# 3V3_VoltageReg.net
KiCad netlist of a schematic drawn in Altium Designer
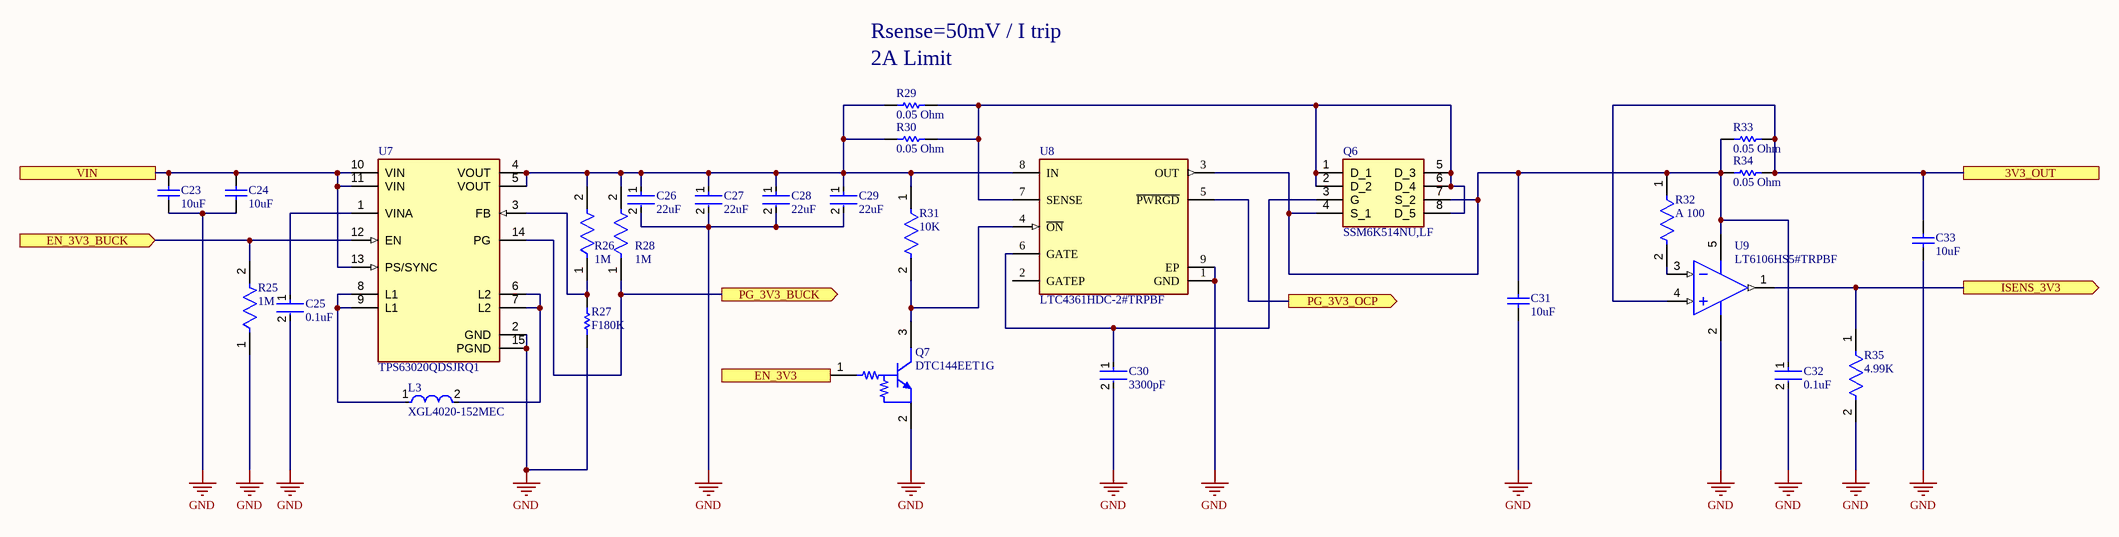
[diagram p0: 3V3_VoltageReg.SchDoc]

(export (version "E")
  (design (tool "Eeschema 10.0.6"))
  (components
    (comp (ref "C23")
      (value "10uF")
      (footprint "CAPC2013X140X45NL15T25")
      (fields (field (name "PART NUMBER") "GRM21BR71A106KE51L") (field (name "MANUFACTURER") "Murata"))
      (libsource (lib "Altium Content Vault") (part "CAP"))
    )
    (comp (ref "C24")
      (value "10uF")
      (footprint "CAPC2013X140X45NL15T25")
      (fields (field (name "PART NUMBER") "GRM21BR71A106KE51L") (field (name "MANUFACTURER") "Murata"))
      (libsource (lib "Altium Content Vault") (part "CAP"))
    )
    (comp (ref "C25")
      (value "0.1uF")
      (footprint "FP-C0603C-CF-MFG")
      (description "CAP CER 0.1UF 50V X7R 0603")
      (fields (field (name "TOLERANCE") "0.1") (field (name "MANUFACTURER") "KEMET"))
      (libsource (lib "Altium Content Vault") (part "b4654b650e69147ec39a6b967a45e02"))
    )
    (comp (ref "C26")
      (value "22uF")
      (footprint "FP-GRM21B-0_2-e0_2_0_7-IPC_C")
      (description "Chip Multilayer Ceramic Capacitors for General Purpose, 0805, 22uF, X7T, +22%/-33%, 20%, 10V")
      (fields (field (name "VOLTAGE") "10V") (field (name "TOLERANCE") "20%"))
      (libsource (lib "Altium Content Vault") (part "b4654b650e69147ec39a6b967a45e02"))
    )
    (comp (ref "C27")
      (value "22uF")
      (footprint "FP-GRM21B-0_2-e0_2_0_7-IPC_C")
      (description "Chip Multilayer Ceramic Capacitors for General Purpose, 0805, 22uF, X7T, +22%/-33%, 20%, 10V")
      (fields (field (name "VOLTAGE") "10V") (field (name "TOLERANCE") "20%"))
      (libsource (lib "Altium Content Vault") (part "b4654b650e69147ec39a6b967a45e02"))
    )
    (comp (ref "C28")
      (value "22uF")
      (footprint "FP-GRM21B-0_2-e0_2_0_7-IPC_C")
      (description "Chip Multilayer Ceramic Capacitors for General Purpose, 0805, 22uF, X7T, +22%/-33%, 20%, 10V")
      (fields (field (name "VOLTAGE") "10V") (field (name "TOLERANCE") "20%"))
      (libsource (lib "Altium Content Vault") (part "b4654b650e69147ec39a6b967a45e02"))
    )
    (comp (ref "C29")
      (value "22uF")
      (footprint "FP-GRM21B-0_2-e0_2_0_7-IPC_C")
      (description "Chip Multilayer Ceramic Capacitors for General Purpose, 0805, 22uF, X7T, +22%/-33%, 20%, 10V")
      (fields (field (name "VOLTAGE") "10V") (field (name "TOLERANCE") "20%"))
      (libsource (lib "Altium Content Vault") (part "b4654b650e69147ec39a6b967a45e02"))
    )
    (comp (ref "C30")
      (value "3300pF")
      (footprint "FP-C0603C-CF-MFG")
      (description "CAP CER 3300PF 50V 5% X7R 0603")
      (fields
        (field (name "MANUFACTURER PART NUMBER") "C0603C332J5RACTU")
        (field (name "MANUFACTURER") "KEMET")
      )
      (libsource (lib "Altium Content Vault") (part "b4654b650e69147ec39a6b967a45e02"))
    )
    (comp (ref "C31")
      (value "10uF")
      (footprint "CAPC2013X140X45NL15T25")
      (fields (field (name "PART NUMBER") "GRM21BR71A106KE51L") (field (name "MANUFACTURER") "Murata"))
      (libsource (lib "Altium Content Vault") (part "CAP"))
    )
    (comp (ref "C32")
      (value "0.1uF")
      (footprint "FP-C0603C-CF-MFG")
      (description "CAP CER 0.1UF 50V X7R 0603")
      (fields (field (name "TOLERANCE") "0.1") (field (name "MANUFACTURER") "KEMET"))
      (libsource (lib "Altium Content Vault") (part "b4654b650e69147ec39a6b967a45e02"))
    )
    (comp (ref "C33")
      (value "10uF")
      (footprint "CAPC2013X140X45NL15T25")
      (fields (field (name "PART NUMBER") "GRM21BR71A106KE51L") (field (name "MANUFACTURER") "Murata"))
      (libsource (lib "Altium Content Vault") (part "CAP"))
    )
    (comp (ref "L3")
      (value "XGL4020-152MEC")
      (footprint "FP-XGL4020-MFG")
      (description "Shielded Power Inductors")
      (fields (field (name "MANUFACTURER") "Coilcraft") (field (name "TOLERANCE") "20%"))
      (libsource (lib "Altium Content Vault") (part "725321dda6339637d4d059423bc1c3c"))
    )
    (comp (ref "Q6")
      (value "SSM6K514NU,LF")
      (footprint "SamacSys:UDFN6B")
      (description "MOSFET (N-Channel)")
      (fields (field (name "MOUSER PART NUMBER") "757-SSM6K514NULF"))
      (libsource (lib "*") (part "SSM6K514NU,LF"))
    )
    (comp (ref "Q7")
      (value "DTC144EET1G")
      (footprint "ONSC-SC-75-3-463-01_V")
      (fields (field (name "MANUFACTURER") "On Semiconductor"))
      (libsource (lib "Altium Content Vault") (part "ONSC-BRT-NPN-B1E2C3-3"))
    )
    (comp (ref "R25")
      (value "1M")
      (footprint "FP-ERJ3EK-IPC_C")
      (description "RES SMD 1M OHM 1% 1/10W 0603")
      (fields (field (name "TOLERANCE") "1%"))
      (libsource (lib "Altium Content Vault") (part "1029c3af85768c4190bb7ad29bc67b5"))
    )
    (comp (ref "R26")
      (value "1M")
      (footprint "FP-ERJ3EK-IPC_C")
      (description "RES SMD 1M OHM 1% 1/10W 0603")
      (fields (field (name "TOLERANCE") "1%"))
      (libsource (lib "Altium Content Vault") (part "1029c3af85768c4190bb7ad29bc67b5"))
    )
    (comp (ref "R27")
      (value "F180K")
      (footprint "RESC1608X55X30ML20T10")
      (fields (field (name "MANUFACTURER") "KOA Speer") (field (name "PART NUMBER") "RK73H1JTTD1803F"))
      (libsource (lib "Altium Content Vault") (part "RES"))
    )
    (comp (ref "R28")
      (value "1M")
      (footprint "FP-ERJ3EK-IPC_C")
      (description "RES SMD 1M OHM 1% 1/10W 0603")
      (fields (field (name "TOLERANCE") "1%"))
      (libsource (lib "Altium Content Vault") (part "1029c3af85768c4190bb7ad29bc67b5"))
    )
    (comp (ref "R29")
      (value "0.05 Ohm")
      (footprint "RESC1608X55X30NL15T15")
      (fields (field (name "MANUFACTURER") "Panasonic") (field (name "PART NUMBER") "ERJ-L03KF50MV"))
      (libsource (lib "Altium Content Vault") (part "RES"))
    )
    (comp (ref "R30")
      (value "0.05 Ohm")
      (footprint "RESC1608X55X30NL15T15")
      (fields (field (name "MANUFACTURER") "Panasonic") (field (name "PART NUMBER") "ERJ-L03KF50MV"))
      (libsource (lib "Altium Content Vault") (part "RES"))
    )
    (comp (ref "R31")
      (value "10K")
      (footprint "FP-RK73B1J-MFG")
      (description "RES 10K OHM 5% 1/10W 0603")
      (fields (field (name "TOLERANCE") "5%"))
      (libsource (lib "Altium Content Vault") (part "1029c3af85768c4190bb7ad29bc67b5"))
    )
    (comp (ref "R32")
      (value "A 100")
      (footprint "FP-ERA3A-IPC_B")
      (description "RES SMD 100 OHM 0.1% 1/10W 0603")
      (fields (field (name "TOLERANCE") "0.1%"))
      (libsource (lib "Altium Content Vault") (part "1029c3af85768c4190bb7ad29bc67b5"))
    )
    (comp (ref "R33")
      (value "0.05 Ohm")
      (footprint "RESC1608X55X30NL15T15")
      (fields (field (name "MANUFACTURER") "Panasonic") (field (name "PART NUMBER") "ERJ-L03KF50MV"))
      (libsource (lib "Altium Content Vault") (part "RES"))
    )
    (comp (ref "R34")
      (value "0.05 Ohm")
      (footprint "RESC1608X55X30NL15T15")
      (fields (field (name "MANUFACTURER") "Panasonic") (field (name "PART NUMBER") "ERJ-L03KF50MV"))
      (libsource (lib "Altium Content Vault") (part "RES"))
    )
    (comp (ref "R35")
      (value "4.99K")
      (footprint "FP-ERA3A-IPC_C")
      (description "RES SMD 4.99KOHM 0.1% 1/10W 0603")
      (fields (field (name "TOLERANCE") "0.1%"))
      (libsource (lib "Altium Content Vault") (part "1029c3af85768c4190bb7ad29bc67b5"))
    )
    (comp (ref "U7")
      (value "TPS63020QDSJRQ1")
      (footprint "FP-DSJ0014A-MFG")
      (description "IC REG BCK BST ADJ 3.5A 14VSON")
      (fields
        (field (name "OCTOPART") "https://octopart.com/tps63020qdsjrq1-texas+instruments-66805608")
        (field (name "MANUFACTURER") "Texas Instruments")
      )
      (libsource (lib "Altium Content Vault") (part "4ac7b32596138e1a7c7f639faf19719"))
    )
    (comp (ref "U8")
      (value "LTC4361HDC-2#TRPBF")
      (footprint "FP-DC8-8-05-08-1719-IPC_C")
      (description "IC OVP/OCP PROTECTION CTLR 8DFN")
      (libsource (lib "Altium Content Vault") (part "fbb45dfe5e09bf71f23ab0fd2a2f1dd"))
    )
    (comp (ref "U9")
      (value "LT6106HS5#TRPBF")
      (footprint "LT-S5-5-TSOT-23_M")
      (fields
        (field (name "MANUFACTURER") "Linear Technology")
        (field (name "LINEAR TECHNOLOGY PART NUMBER") "LT6106")
      )
      (libsource (lib "Altium Content Vault") (part "LT-LT6106-LTC6101HV-5"))
    )
  )
  (nets
    (net (code "1") (name "/3V3_OUT") (class "Default")
      (node (ref "C33") (pin "2") (pinfunction "2_2") (pintype "passive"))
      (node (ref "R33") (pin "2") (pinfunction "2_2") (pintype "passive"))
      (node (ref "R34") (pin "2") (pinfunction "2_2") (pintype "passive"))
      (node (ref "U9") (pin "4") (pinfunction "+IN_4") (pintype "input"))
    )
    (net (code "2") (name "/EN_3V3") (class "Default")
      (node (ref "Q7") (pin "1") (pinfunction "B_1") (pintype "passive"))
    )
    (net (code "3") (name "/EN_3V3_BUCK") (class "Default")
      (node (ref "R25") (pin "2") (pinfunction "2_2") (pintype "passive"))
      (node (ref "U7") (pin "12") (pinfunction "EN_12") (pintype "input"))
    )
    (net (code "4") (name "/ISENS_3V3") (class "Default")
      (node (ref "R35") (pin "1") (pinfunction "1_1") (pintype "passive"))
      (node (ref "U9") (pin "1") (pinfunction "OUT_1") (pintype "output"))
    )
    (net (code "5") (name "/PG_3V3_BUCK") (class "Default")
      (node (ref "R28") (pin "1") (pinfunction "1_1") (pintype "passive"))
      (node (ref "U7") (pin "14") (pinfunction "PG_14") (pintype "open_collector"))
    )
    (net (code "6") (name "/PG_3V3_OCP") (class "Default")
      (node (ref "U8") (pin "5") (pinfunction "~{PWRGD}_5") (pintype "open_collector"))
    )
    (net (code "7") (name "/VIN") (class "Default")
      (node (ref "C23") (pin "2") (pinfunction "2_2") (pintype "passive"))
      (node (ref "C24") (pin "2") (pinfunction "2_2") (pintype "passive"))
      (node (ref "U7") (pin "10") (pinfunction "VIN_10") (pintype "power_in"))
      (node (ref "U7") (pin "11") (pinfunction "VIN_11") (pintype "power_in"))
      (node (ref "U7") (pin "13") (pinfunction "PS/SYNC_13") (pintype "input"))
    )
    (net (code "8") (name "GND") (class "Default")
      (node (ref "C23") (pin "1") (pinfunction "1_1") (pintype "passive"))
      (node (ref "C24") (pin "1") (pinfunction "1_1") (pintype "passive"))
      (node (ref "C25") (pin "2") (pinfunction "2_2") (pintype "passive"))
      (node (ref "C26") (pin "2") (pinfunction "2_2") (pintype "passive"))
      (node (ref "C27") (pin "2") (pinfunction "2_2") (pintype "passive"))
      (node (ref "C28") (pin "2") (pinfunction "2_2") (pintype "passive"))
      (node (ref "C29") (pin "2") (pinfunction "2_2") (pintype "passive"))
      (node (ref "C30") (pin "2") (pinfunction "2_2") (pintype "passive"))
      (node (ref "C31") (pin "1") (pinfunction "1_1") (pintype "passive"))
      (node (ref "C32") (pin "2") (pinfunction "2_2") (pintype "passive"))
      (node (ref "C33") (pin "1") (pinfunction "1_1") (pintype "passive"))
      (node (ref "Q7") (pin "2") (pinfunction "E_2") (pintype "passive"))
      (node (ref "R25") (pin "1") (pinfunction "1_1") (pintype "passive"))
      (node (ref "R27") (pin "1") (pinfunction "1_1") (pintype "passive"))
      (node (ref "R35") (pin "2") (pinfunction "2_2") (pintype "passive"))
      (node (ref "U7") (pin "15") (pinfunction "PGND_15") (pintype "power_in"))
      (node (ref "U7") (pin "2") (pinfunction "GND_2") (pintype "power_in"))
      (node (ref "U8") (pin "1") (pinfunction "GND_1") (pintype "power_in"))
      (node (ref "U8") (pin "9") (pinfunction "EP_9") (pintype "power_in"))
      (node (ref "U9") (pin "2") (pinfunction "V-_2") (pintype "power_in"))
    )
    (net (code "9") (name "Net-(L3-Pad1)") (class "Default")
      (node (ref "L3") (pin "1") (pinfunction "1_1") (pintype "passive"))
      (node (ref "U7") (pin "8") (pinfunction "L1_8") (pintype "passive"))
      (node (ref "U7") (pin "9") (pinfunction "L1_9") (pintype "passive"))
    )
    (net (code "10") (name "Net-(L3-Pad2)") (class "Default")
      (node (ref "L3") (pin "2") (pinfunction "2_2") (pintype "passive"))
      (node (ref "U7") (pin "6") (pinfunction "L2_6") (pintype "passive"))
      (node (ref "U7") (pin "7") (pinfunction "L2_7") (pintype "passive"))
    )
    (net (code "11") (name "Net-(Q6-D_1)") (class "Default")
      (node (ref "Q6") (pin "1") (pinfunction "D_1_1") (pintype "passive"))
      (node (ref "Q6") (pin "2") (pinfunction "D_2_2") (pintype "passive"))
      (node (ref "Q6") (pin "5") (pinfunction "D_3_5") (pintype "passive"))
      (node (ref "Q6") (pin "6") (pinfunction "D_4_6") (pintype "passive"))
      (node (ref "Q6") (pin "8") (pinfunction "D_5_8") (pintype "passive"))
      (node (ref "R29") (pin "2") (pinfunction "2_2") (pintype "passive"))
      (node (ref "R30") (pin "2") (pinfunction "2_2") (pintype "passive"))
      (node (ref "U8") (pin "7") (pinfunction "SENSE_7") (pintype "passive"))
    )
    (net (code "12") (name "Net-(Q6-G)") (class "Default")
      (node (ref "C30") (pin "1") (pinfunction "1_1") (pintype "passive"))
      (node (ref "Q6") (pin "3") (pinfunction "G_3") (pintype "passive"))
      (node (ref "U8") (pin "6") (pinfunction "GATE_6") (pintype "passive"))
    )
    (net (code "13") (name "Net-(Q6-S_1)") (class "Default")
      (node (ref "C31") (pin "2") (pinfunction "2_2") (pintype "passive"))
      (node (ref "C32") (pin "1") (pinfunction "1_1") (pintype "passive"))
      (node (ref "Q6") (pin "4") (pinfunction "S_1_4") (pintype "passive"))
      (node (ref "Q6") (pin "7") (pinfunction "S_2_7") (pintype "passive"))
      (node (ref "R32") (pin "1") (pinfunction "1_1") (pintype "passive"))
      (node (ref "R33") (pin "1") (pinfunction "1_1") (pintype "passive"))
      (node (ref "R34") (pin "1") (pinfunction "1_1") (pintype "passive"))
      (node (ref "U8") (pin "3") (pinfunction "OUT_3") (pintype "output"))
      (node (ref "U9") (pin "5") (pinfunction "V+_5") (pintype "power_in"))
    )
    (net (code "14") (name "Net-(Q7-C)") (class "Default")
      (node (ref "Q7") (pin "3") (pinfunction "C_3") (pintype "passive"))
      (node (ref "R31") (pin "2") (pinfunction "2_2") (pintype "passive"))
      (node (ref "U8") (pin "4") (pinfunction "~{ON}_4") (pintype "input"))
    )
    (net (code "15") (name "Net-(U7-FB)") (class "Default")
      (node (ref "R26") (pin "1") (pinfunction "1_1") (pintype "passive"))
      (node (ref "R27") (pin "2") (pinfunction "2_2") (pintype "passive"))
      (node (ref "U7") (pin "3") (pinfunction "FB_3") (pintype "input"))
    )
    (net (code "16") (name "Net-(U7-VINA)") (class "Default")
      (node (ref "C25") (pin "1") (pinfunction "1_1") (pintype "passive"))
      (node (ref "U7") (pin "1") (pinfunction "VINA_1") (pintype "power_in"))
    )
    (net (code "17") (name "Net-(U8-IN)") (class "Default")
      (node (ref "C26") (pin "1") (pinfunction "1_1") (pintype "passive"))
      (node (ref "C27") (pin "1") (pinfunction "1_1") (pintype "passive"))
      (node (ref "C28") (pin "1") (pinfunction "1_1") (pintype "passive"))
      (node (ref "C29") (pin "1") (pinfunction "1_1") (pintype "passive"))
      (node (ref "R26") (pin "2") (pinfunction "2_2") (pintype "passive"))
      (node (ref "R28") (pin "2") (pinfunction "2_2") (pintype "passive"))
      (node (ref "R29") (pin "1") (pinfunction "1_1") (pintype "passive"))
      (node (ref "R30") (pin "1") (pinfunction "1_1") (pintype "passive"))
      (node (ref "R31") (pin "1") (pinfunction "1_1") (pintype "passive"))
      (node (ref "U7") (pin "4") (pinfunction "VOUT_4") (pintype "power_in"))
      (node (ref "U7") (pin "5") (pinfunction "VOUT_5") (pintype "power_in"))
      (node (ref "U8") (pin "8") (pinfunction "IN_8") (pintype "power_in"))
    )
    (net (code "18") (name "Net-(U9--IN)") (class "Default")
      (node (ref "R32") (pin "2") (pinfunction "2_2") (pintype "passive"))
      (node (ref "U9") (pin "3") (pinfunction "-IN_3") (pintype "input"))
    )
    (net (code "19") (name "unconnected-(U8-GATEP-Pad2)") (class "Default")
      (node (ref "U8") (pin "2") (pinfunction "GATEP_2") (pintype "passive"))
    )
  )
)
